# MCU.net
KiCad netlist of a schematic drawn in Altium Designer
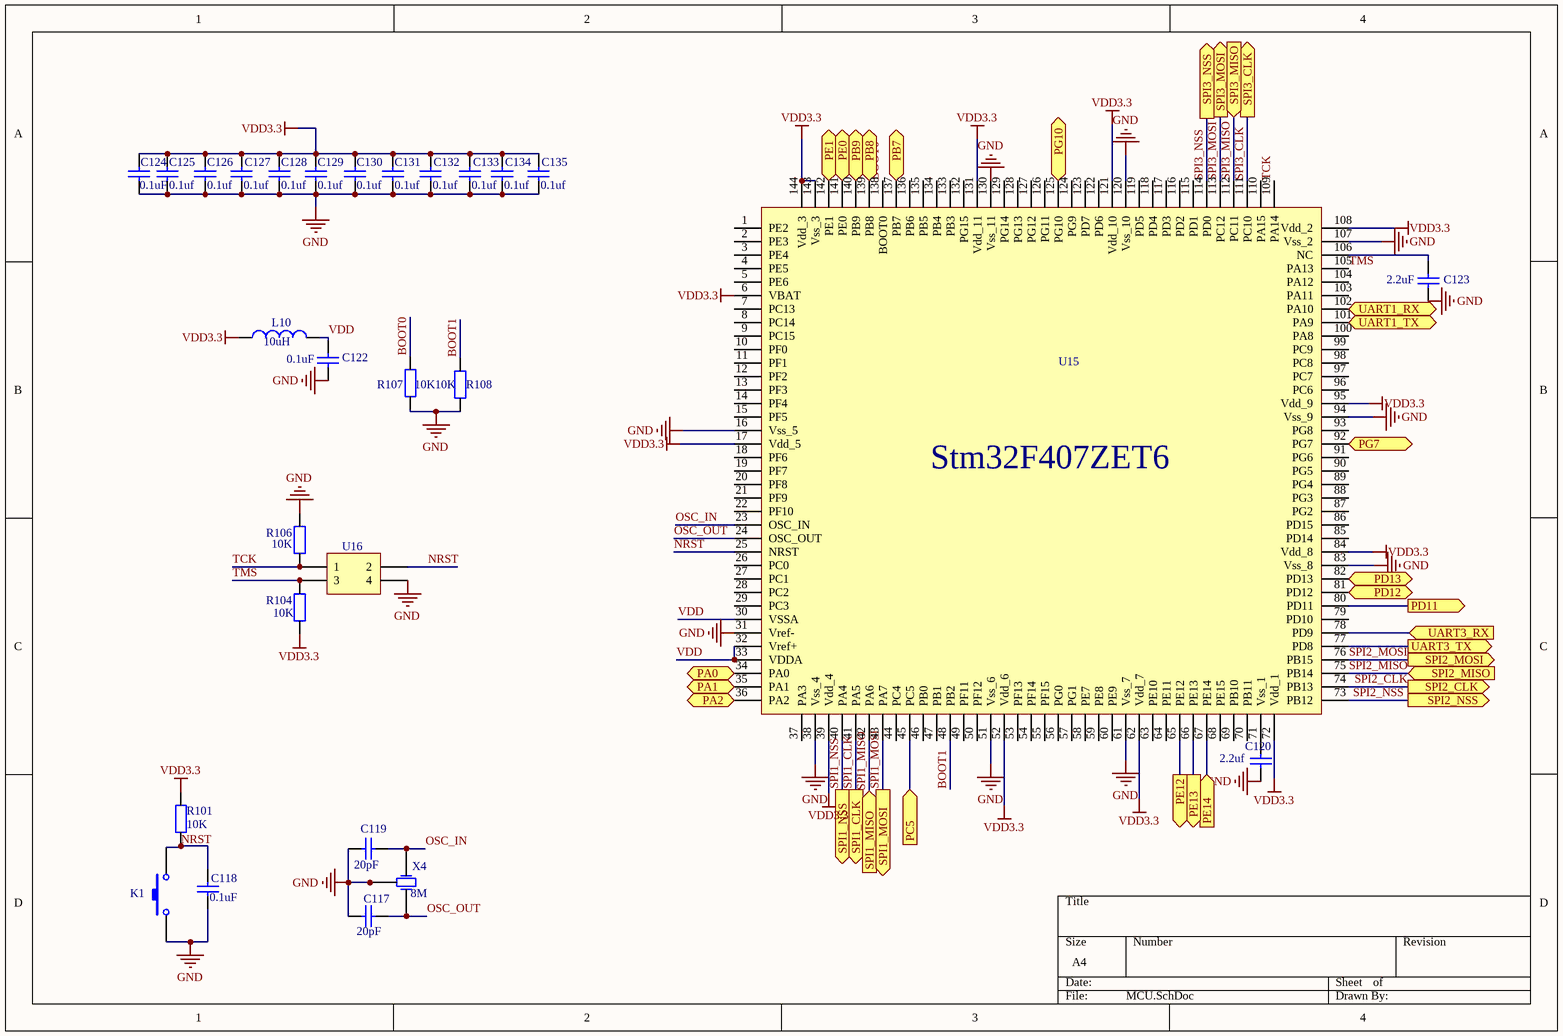
[diagram p0: MCU.SchDoc]

(export (version "E")
  (design (tool "Eeschema 10.0.6"))
  (components
    (comp (ref "C117")
      (value "20pF")
      (footprint "0603")
      (fields (field (name "Comment") "Capacitor-0805"))
      (libsource (lib "原理图库") (part "Capacitor-0805"))
    )
    (comp (ref "C118")
      (value "0.1uF")
      (footprint "0603")
      (fields (field (name "Comment") "Capacitor-0805"))
      (libsource (lib "原理图库") (part "Capacitor-0805"))
    )
    (comp (ref "C119")
      (value "20pF")
      (footprint "0603")
      (fields (field (name "Comment") "Capacitor-0805"))
      (libsource (lib "原理图库") (part "Capacitor-0805"))
    )
    (comp (ref "C120")
      (value "2.2uf")
      (footprint "0603")
      (fields (field (name "Comment") "Capacitor-0603"))
      (libsource (lib "原理图库") (part "Capacitor-0603"))
    )
    (comp (ref "C122")
      (value "0.1uF")
      (footprint "0603")
      (fields (field (name "Comment") "Capacitor-0805"))
      (libsource (lib "集成库—大岐") (part "Capacitor-0805"))
    )
    (comp (ref "C123")
      (value "2.2uF")
      (footprint "0603")
      (fields (field (name "Comment") "Capacitor-0603"))
      (libsource (lib "原理图库") (part "Capacitor-0603"))
    )
    (comp (ref "C124")
      (value "0.1uF")
      (footprint "0603")
      (fields (field (name "Comment") "Capacitor-0805"))
      (libsource (lib "集成库—大岐") (part "Capacitor-0805"))
    )
    (comp (ref "C125")
      (value "0.1uf")
      (footprint "0603")
      (fields (field (name "Comment") "Capacitor-0805"))
      (libsource (lib "集成库—大岐") (part "Capacitor-0805"))
    )
    (comp (ref "C126")
      (value "0.1uf")
      (footprint "0603")
      (fields (field (name "Comment") "Capacitor-0805"))
      (libsource (lib "集成库—大岐") (part "Capacitor-0805"))
    )
    (comp (ref "C127")
      (value "0.1uf")
      (footprint "0603")
      (fields (field (name "Comment") "Capacitor-0805"))
      (libsource (lib "集成库—大岐") (part "Capacitor-0805"))
    )
    (comp (ref "C128")
      (value "0.1uf")
      (footprint "0603")
      (fields (field (name "Comment") "Capacitor-0805"))
      (libsource (lib "集成库—大岐") (part "Capacitor-0805"))
    )
    (comp (ref "C129")
      (value "0.1uf")
      (footprint "0603")
      (fields (field (name "Comment") "Capacitor-0805"))
      (libsource (lib "集成库—大岐") (part "Capacitor-0805"))
    )
    (comp (ref "C130")
      (value "0.1uf")
      (footprint "0603")
      (fields (field (name "Comment") "Capacitor-0805"))
      (libsource (lib "集成库—大岐") (part "Capacitor-0805"))
    )
    (comp (ref "C131")
      (value "0.1uf")
      (footprint "0603")
      (fields (field (name "Comment") "Capacitor-0805"))
      (libsource (lib "集成库—大岐") (part "Capacitor-0805"))
    )
    (comp (ref "C132")
      (value "0.1uf")
      (footprint "0603")
      (fields (field (name "Comment") "Capacitor-0805"))
      (libsource (lib "集成库—大岐") (part "Capacitor-0805"))
    )
    (comp (ref "C133")
      (value "0.1uf")
      (footprint "0603")
      (fields (field (name "Comment") "Capacitor-0805"))
      (libsource (lib "集成库—大岐") (part "Capacitor-0805"))
    )
    (comp (ref "C134")
      (value "0.1uf")
      (footprint "0603")
      (fields (field (name "Comment") "Capacitor-0805"))
      (libsource (lib "集成库—大岐") (part "Capacitor-0805"))
    )
    (comp (ref "C135")
      (value "0.1uf")
      (footprint "0603")
      (fields (field (name "Comment") "Capacitor-0805"))
      (libsource (lib "集成库—大岐") (part "Capacitor-0805"))
    )
    (comp (ref "K1") (value "按键") (footprint "贴片按键") (libsource (lib "原理图库") (part "按键")))
    (comp (ref "L10")
      (value "10uH")
      (footprint "0805")
      (fields (field (name "Comment") "Inductor"))
      (libsource (lib "集成库—大岐") (part "Inductor"))
    )
    (comp (ref "R101")
      (value "10K")
      (footprint "0603")
      (fields (field (name "Comment") "Resistor-0805"))
      (libsource (lib "原理图库") (part "Resistor-0805"))
    )
    (comp (ref "R104")
      (value "10K")
      (footprint "0603")
      (fields (field (name "Comment") "Resistor-0805"))
      (libsource (lib "原理图库") (part "Resistor-0805"))
    )
    (comp (ref "R106")
      (value "10K")
      (footprint "0603")
      (fields (field (name "Comment") "Resistor-0805"))
      (libsource (lib "原理图库") (part "Resistor-0805"))
    )
    (comp (ref "R107")
      (value "10K")
      (footprint "0603")
      (fields (field (name "Comment") "Resistor-0805"))
      (libsource (lib "集成库—大岐") (part "Resistor-0805"))
    )
    (comp (ref "R108")
      (value "10K")
      (footprint "0603")
      (fields (field (name "Comment") "Resistor-0805"))
      (libsource (lib "集成库—大岐") (part "Resistor-0805"))
    )
    (comp (ref "U15")
      (value "STM32F407ZET6")
      (footprint "Stm32f407ZET6 - duplicate")
      (libsource (lib "原理图库") (part "STM32F407ZET6"))
    )
    (comp (ref "U16")
      (value "Header 2X2")
      (footprint "HDR2X2")
      (description "Header, 2-Pin, Dual row")
      (fields (field (name "PUBLISHER") "Altium Limited"))
      (libsource (lib "Miscellaneous Connectors") (part "Header 2X2"))
    )
    (comp (ref "X4")
      (value "8M")
      (footprint "3225无源晶振")
      (fields (field (name "Comment") "3225无源晶振"))
      (libsource (lib "原理图库") (part "3225无源晶振"))
    )
  )
  (nets
    (net (code "1") (name "/BOOT0") (class "Default")
      (node (ref "R107") (pin "2") (pinfunction "2_2") (pintype "passive"))
      (node (ref "U15") (pin "138") (pinfunction "BOOT0_138") (pintype "passive"))
    )
    (net (code "2") (name "/BOOT1") (class "Default")
      (node (ref "R108") (pin "2") (pinfunction "2_2") (pintype "passive"))
      (node (ref "U15") (pin "48") (pinfunction "PB2_48") (pintype "passive"))
    )
    (net (code "3") (name "/NRST") (class "Default")
      (node (ref "C118") (pin "2") (pinfunction "2_2") (pintype "passive"))
      (node (ref "K1") (pin "2") (pinfunction "2_2") (pintype "passive"))
      (node (ref "R101") (pin "1") (pinfunction "1_1") (pintype "passive"))
      (node (ref "U15") (pin "25") (pinfunction "NRST_25") (pintype "passive"))
      (node (ref "U16") (pin "2") (pinfunction "2_2") (pintype "passive"))
    )
    (net (code "4") (name "/OSC_IN") (class "Default")
      (node (ref "C119") (pin "2") (pinfunction "2_2") (pintype "passive"))
      (node (ref "U15") (pin "23") (pinfunction "OSC_IN_23") (pintype "passive"))
      (node (ref "X4") (pin "1") (pinfunction "OSC1_1") (pintype "passive"))
    )
    (net (code "5") (name "/OSC_OUT") (class "Default")
      (node (ref "C117") (pin "2") (pinfunction "2_2") (pintype "passive"))
      (node (ref "U15") (pin "24") (pinfunction "OSC_OUT_24") (pintype "passive"))
      (node (ref "X4") (pin "3") (pinfunction "OSC2_3") (pintype "passive"))
    )
    (net (code "6") (name "/PA0") (class "Default")
      (node (ref "U15") (pin "34") (pinfunction "PA0_34") (pintype "passive"))
    )
    (net (code "7") (name "/PA1") (class "Default")
      (node (ref "U15") (pin "35") (pinfunction "PA1_35") (pintype "passive"))
    )
    (net (code "8") (name "/PA2") (class "Default")
      (node (ref "U15") (pin "36") (pinfunction "PA2_36") (pintype "passive"))
    )
    (net (code "9") (name "/PB7") (class "Default")
      (node (ref "U15") (pin "137") (pinfunction "PB7_137") (pintype "passive"))
    )
    (net (code "10") (name "/PB8") (class "Default")
      (node (ref "U15") (pin "139") (pinfunction "PB8_139") (pintype "passive"))
    )
    (net (code "11") (name "/PB9") (class "Default")
      (node (ref "U15") (pin "140") (pinfunction "PB9_140") (pintype "passive"))
    )
    (net (code "12") (name "/PC5") (class "Default")
      (node (ref "U15") (pin "45") (pinfunction "PC5_45") (pintype "passive"))
    )
    (net (code "13") (name "/PD11") (class "Default")
      (node (ref "U15") (pin "80") (pinfunction "PD11_80") (pintype "passive"))
    )
    (net (code "14") (name "/PD12") (class "Default")
      (node (ref "U15") (pin "81") (pinfunction "PD12_81") (pintype "passive"))
    )
    (net (code "15") (name "/PD13") (class "Default")
      (node (ref "U15") (pin "82") (pinfunction "PD13_82") (pintype "passive"))
    )
    (net (code "16") (name "/PE0") (class "Default")
      (node (ref "U15") (pin "141") (pinfunction "PE0_141") (pintype "passive"))
    )
    (net (code "17") (name "/PE1") (class "Default")
      (node (ref "U15") (pin "142") (pinfunction "PE1_142") (pintype "passive"))
    )
    (net (code "18") (name "/PE12") (class "Default")
      (node (ref "U15") (pin "65") (pinfunction "PE12_65") (pintype "passive"))
    )
    (net (code "19") (name "/PE13") (class "Default")
      (node (ref "U15") (pin "66") (pinfunction "PE13_66") (pintype "passive"))
    )
    (net (code "20") (name "/PE14") (class "Default")
      (node (ref "U15") (pin "67") (pinfunction "PE14_67") (pintype "passive"))
    )
    (net (code "21") (name "/PG7") (class "Default")
      (node (ref "U15") (pin "92") (pinfunction "PG7_92") (pintype "passive"))
    )
    (net (code "22") (name "/PG10") (class "Default")
      (node (ref "U15") (pin "125") (pinfunction "PG10_125") (pintype "passive"))
    )
    (net (code "23") (name "/SPI1_CLK") (class "Default")
      (node (ref "U15") (pin "41") (pinfunction "PA5_41") (pintype "passive"))
    )
    (net (code "24") (name "/SPI1_MISO") (class "Default")
      (node (ref "U15") (pin "42") (pinfunction "PA6_42") (pintype "passive"))
    )
    (net (code "25") (name "/SPI1_MOSI") (class "Default")
      (node (ref "U15") (pin "43") (pinfunction "PA7_43") (pintype "passive"))
    )
    (net (code "26") (name "/SPI1_NSS") (class "Default")
      (node (ref "U15") (pin "40") (pinfunction "PA4_40") (pintype "passive"))
    )
    (net (code "27") (name "/SPI2_CLK") (class "Default")
      (node (ref "U15") (pin "74") (pinfunction "PB13_74") (pintype "passive"))
    )
    (net (code "28") (name "/SPI2_MISO") (class "Default")
      (node (ref "U15") (pin "75") (pinfunction "PB14_75") (pintype "passive"))
    )
    (net (code "29") (name "/SPI2_MOSI") (class "Default")
      (node (ref "U15") (pin "76") (pinfunction "PB15_76") (pintype "passive"))
    )
    (net (code "30") (name "/SPI2_NSS") (class "Default")
      (node (ref "U15") (pin "73") (pinfunction "PB12_73") (pintype "passive"))
    )
    (net (code "31") (name "/SPI3_CLK") (class "Default")
      (node (ref "U15") (pin "111") (pinfunction "PC10_111") (pintype "passive"))
    )
    (net (code "32") (name "/SPI3_MISO") (class "Default")
      (node (ref "U15") (pin "112") (pinfunction "PC11_112") (pintype "passive"))
    )
    (net (code "33") (name "/SPI3_MOSI") (class "Default")
      (node (ref "U15") (pin "113") (pinfunction "PC12_113") (pintype "passive"))
    )
    (net (code "34") (name "/SPI3_NSS") (class "Default")
      (node (ref "U15") (pin "114") (pinfunction "PD0_114") (pintype "passive"))
    )
    (net (code "35") (name "/TCK") (class "Default")
      (node (ref "R106") (pin "1") (pinfunction "1_1") (pintype "passive"))
      (node (ref "U15") (pin "109") (pinfunction "PA14_109") (pintype "passive"))
      (node (ref "U16") (pin "1") (pinfunction "1_1") (pintype "passive"))
    )
    (net (code "36") (name "/TMS") (class "Default")
      (node (ref "R104") (pin "2") (pinfunction "2_2") (pintype "passive"))
      (node (ref "U15") (pin "105") (pinfunction "PA13_105") (pintype "passive"))
      (node (ref "U16") (pin "3") (pinfunction "3_3") (pintype "passive"))
    )
    (net (code "37") (name "/UART1_RX") (class "Default")
      (node (ref "U15") (pin "102") (pinfunction "PA10_102") (pintype "passive"))
    )
    (net (code "38") (name "/UART1_TX") (class "Default")
      (node (ref "U15") (pin "101") (pinfunction "PA9_101") (pintype "passive"))
    )
    (net (code "39") (name "/UART3_RX") (class "Default")
      (node (ref "U15") (pin "78") (pinfunction "PD9_78") (pintype "passive"))
    )
    (net (code "40") (name "/UART3_TX") (class "Default")
      (node (ref "U15") (pin "77") (pinfunction "PD8_77") (pintype "passive"))
    )
    (net (code "41") (name "/VDD") (class "Default")
      (node (ref "C122") (pin "2") (pinfunction "2_2") (pintype "passive"))
      (node (ref "L10") (pin "2") (pinfunction "2_2") (pintype "passive"))
      (node (ref "U15") (pin "30") (pinfunction "VSSA_30") (pintype "passive"))
      (node (ref "U15") (pin "32") (pinfunction "Vref+_32") (pintype "passive"))
      (node (ref "U15") (pin "33") (pinfunction "VDDA_33") (pintype "passive"))
    )
    (net (code "42") (name "GND") (class "Default")
      (node (ref "C117") (pin "1") (pinfunction "1_1") (pintype "passive"))
      (node (ref "C118") (pin "1") (pinfunction "1_1") (pintype "passive"))
      (node (ref "C119") (pin "1") (pinfunction "1_1") (pintype "passive"))
      (node (ref "C120") (pin "1") (pinfunction "1_1") (pintype "passive"))
      (node (ref "C122") (pin "1") (pinfunction "1_1") (pintype "passive"))
      (node (ref "C123") (pin "1") (pinfunction "1_1") (pintype "passive"))
      (node (ref "C124") (pin "1") (pinfunction "1_1") (pintype "passive"))
      (node (ref "C125") (pin "1") (pinfunction "1_1") (pintype "passive"))
      (node (ref "C126") (pin "1") (pinfunction "1_1") (pintype "passive"))
      (node (ref "C127") (pin "1") (pinfunction "1_1") (pintype "passive"))
      (node (ref "C128") (pin "1") (pinfunction "1_1") (pintype "passive"))
      (node (ref "C129") (pin "1") (pinfunction "1_1") (pintype "passive"))
      (node (ref "C130") (pin "1") (pinfunction "1_1") (pintype "passive"))
      (node (ref "C131") (pin "1") (pinfunction "1_1") (pintype "passive"))
      (node (ref "C132") (pin "1") (pinfunction "1_1") (pintype "passive"))
      (node (ref "C133") (pin "1") (pinfunction "1_1") (pintype "passive"))
      (node (ref "C134") (pin "1") (pinfunction "1_1") (pintype "passive"))
      (node (ref "C135") (pin "1") (pinfunction "1_1") (pintype "passive"))
      (node (ref "K1") (pin "1") (pinfunction "1_1") (pintype "passive"))
      (node (ref "R106") (pin "2") (pinfunction "2_2") (pintype "passive"))
      (node (ref "R107") (pin "1") (pinfunction "1_1") (pintype "passive"))
      (node (ref "R108") (pin "1") (pinfunction "1_1") (pintype "passive"))
      (node (ref "U15") (pin "107") (pinfunction "Vss_2_107") (pintype "passive"))
      (node (ref "U15") (pin "120") (pinfunction "Vss_10_120") (pintype "passive"))
      (node (ref "U15") (pin "130") (pinfunction "Vss_11_130") (pintype "passive"))
      (node (ref "U15") (pin "16") (pinfunction "Vss_5_16") (pintype "passive"))
      (node (ref "U15") (pin "31") (pinfunction "Vref-_31") (pintype "passive"))
      (node (ref "U15") (pin "38") (pinfunction "Vss_4_38") (pintype "passive"))
      (node (ref "U15") (pin "51") (pinfunction "Vss_6_51") (pintype "passive"))
      (node (ref "U15") (pin "61") (pinfunction "Vss_7_61") (pintype "passive"))
      (node (ref "U15") (pin "83") (pinfunction "Vss_8_83") (pintype "passive"))
      (node (ref "U15") (pin "94") (pinfunction "Vss_9_94") (pintype "passive"))
      (node (ref "U16") (pin "4") (pinfunction "4_4") (pintype "passive"))
      (node (ref "X4") (pin "2") (pinfunction "GND_2") (pintype "passive"))
      (node (ref "X4") (pin "4") (pinfunction "GND_4") (pintype "passive"))
    )
    (net (code "43") (name "Net-(U15-NC)") (class "Default")
      (node (ref "C123") (pin "2") (pinfunction "2_2") (pintype "passive"))
      (node (ref "U15") (pin "106") (pinfunction "NC_106") (pintype "passive"))
    )
    (net (code "44") (name "Net-(U15-Vss_1)") (class "Default")
      (node (ref "C120") (pin "2") (pinfunction "2_2") (pintype "passive"))
      (node (ref "U15") (pin "71") (pinfunction "Vss_1_71") (pintype "passive"))
    )
    (net (code "45") (name "VDD3.3") (class "Default")
      (node (ref "C124") (pin "2") (pinfunction "2_2") (pintype "passive"))
      (node (ref "C125") (pin "2") (pinfunction "2_2") (pintype "passive"))
      (node (ref "C126") (pin "2") (pinfunction "2_2") (pintype "passive"))
      (node (ref "C127") (pin "2") (pinfunction "2_2") (pintype "passive"))
      (node (ref "C128") (pin "2") (pinfunction "2_2") (pintype "passive"))
      (node (ref "C129") (pin "2") (pinfunction "2_2") (pintype "passive"))
      (node (ref "C130") (pin "2") (pinfunction "2_2") (pintype "passive"))
      (node (ref "C131") (pin "2") (pinfunction "2_2") (pintype "passive"))
      (node (ref "C132") (pin "2") (pinfunction "2_2") (pintype "passive"))
      (node (ref "C133") (pin "2") (pinfunction "2_2") (pintype "passive"))
      (node (ref "C134") (pin "2") (pinfunction "2_2") (pintype "passive"))
      (node (ref "C135") (pin "2") (pinfunction "2_2") (pintype "passive"))
      (node (ref "L10") (pin "1") (pinfunction "1_1") (pintype "passive"))
      (node (ref "R101") (pin "2") (pinfunction "2_2") (pintype "passive"))
      (node (ref "R104") (pin "1") (pinfunction "1_1") (pintype "passive"))
      (node (ref "U15") (pin "108") (pinfunction "Vdd_2_108") (pintype "passive"))
      (node (ref "U15") (pin "121") (pinfunction "Vdd_10_121") (pintype "passive"))
      (node (ref "U15") (pin "131") (pinfunction "Vdd_11_131") (pintype "passive"))
      (node (ref "U15") (pin "143") (pinfunction "Vss_3_143") (pintype "passive"))
      (node (ref "U15") (pin "144") (pinfunction "Vdd_3_144") (pintype "passive"))
      (node (ref "U15") (pin "17") (pinfunction "Vdd_5_17") (pintype "passive"))
      (node (ref "U15") (pin "39") (pinfunction "Vdd_4_39") (pintype "passive"))
      (node (ref "U15") (pin "52") (pinfunction "Vdd_6_52") (pintype "passive"))
      (node (ref "U15") (pin "6") (pinfunction "VBAT_6") (pintype "passive"))
      (node (ref "U15") (pin "62") (pinfunction "Vdd_7_62") (pintype "passive"))
      (node (ref "U15") (pin "72") (pinfunction "Vdd_1_72") (pintype "passive"))
      (node (ref "U15") (pin "84") (pinfunction "Vdd_8_84") (pintype "passive"))
      (node (ref "U15") (pin "95") (pinfunction "Vdd_9_95") (pintype "passive"))
    )
    (net (code "46") (name "unconnected-(U15-PA3-Pad37)") (class "Default")
      (node (ref "U15") (pin "37") (pinfunction "PA3_37") (pintype "passive"))
    )
    (net (code "47") (name "unconnected-(U15-PA8-Pad100)") (class "Default")
      (node (ref "U15") (pin "100") (pinfunction "PA8_100") (pintype "passive"))
    )
    (net (code "48") (name "unconnected-(U15-PA11-Pad103)") (class "Default")
      (node (ref "U15") (pin "103") (pinfunction "PA11_103") (pintype "passive"))
    )
    (net (code "49") (name "unconnected-(U15-PA12-Pad104)") (class "Default")
      (node (ref "U15") (pin "104") (pinfunction "PA12_104") (pintype "passive"))
    )
    (net (code "50") (name "unconnected-(U15-PA15-Pad110)") (class "Default")
      (node (ref "U15") (pin "110") (pinfunction "PA15_110") (pintype "passive"))
    )
    (net (code "51") (name "unconnected-(U15-PB0-Pad46)") (class "Default")
      (node (ref "U15") (pin "46") (pinfunction "PB0_46") (pintype "passive"))
    )
    (net (code "52") (name "unconnected-(U15-PB1-Pad47)") (class "Default")
      (node (ref "U15") (pin "47") (pinfunction "PB1_47") (pintype "passive"))
    )
    (net (code "53") (name "unconnected-(U15-PB3-Pad133)") (class "Default")
      (node (ref "U15") (pin "133") (pinfunction "PB3_133") (pintype "passive"))
    )
    (net (code "54") (name "unconnected-(U15-PB4-Pad134)") (class "Default")
      (node (ref "U15") (pin "134") (pinfunction "PB4_134") (pintype "passive"))
    )
    (net (code "55") (name "unconnected-(U15-PB5-Pad135)") (class "Default")
      (node (ref "U15") (pin "135") (pinfunction "PB5_135") (pintype "passive"))
    )
    (net (code "56") (name "unconnected-(U15-PB6-Pad136)") (class "Default")
      (node (ref "U15") (pin "136") (pinfunction "PB6_136") (pintype "passive"))
    )
    (net (code "57") (name "unconnected-(U15-PB10-Pad69)") (class "Default")
      (node (ref "U15") (pin "69") (pinfunction "PB10_69") (pintype "passive"))
    )
    (net (code "58") (name "unconnected-(U15-PB11-Pad70)") (class "Default")
      (node (ref "U15") (pin "70") (pinfunction "PB11_70") (pintype "passive"))
    )
    (net (code "59") (name "unconnected-(U15-PC0-Pad26)") (class "Default")
      (node (ref "U15") (pin "26") (pinfunction "PC0_26") (pintype "passive"))
    )
    (net (code "60") (name "unconnected-(U15-PC1-Pad27)") (class "Default")
      (node (ref "U15") (pin "27") (pinfunction "PC1_27") (pintype "passive"))
    )
    (net (code "61") (name "unconnected-(U15-PC2-Pad28)") (class "Default")
      (node (ref "U15") (pin "28") (pinfunction "PC2_28") (pintype "passive"))
    )
    (net (code "62") (name "unconnected-(U15-PC3-Pad29)") (class "Default")
      (node (ref "U15") (pin "29") (pinfunction "PC3_29") (pintype "passive"))
    )
    (net (code "63") (name "unconnected-(U15-PC4-Pad44)") (class "Default")
      (node (ref "U15") (pin "44") (pinfunction "PC4_44") (pintype "passive"))
    )
    (net (code "64") (name "unconnected-(U15-PC6-Pad96)") (class "Default")
      (node (ref "U15") (pin "96") (pinfunction "PC6_96") (pintype "passive"))
    )
    (net (code "65") (name "unconnected-(U15-PC7-Pad97)") (class "Default")
      (node (ref "U15") (pin "97") (pinfunction "PC7_97") (pintype "passive"))
    )
    (net (code "66") (name "unconnected-(U15-PC8-Pad98)") (class "Default")
      (node (ref "U15") (pin "98") (pinfunction "PC8_98") (pintype "passive"))
    )
    (net (code "67") (name "unconnected-(U15-PC9-Pad99)") (class "Default")
      (node (ref "U15") (pin "99") (pinfunction "PC9_99") (pintype "passive"))
    )
    (net (code "68") (name "unconnected-(U15-PC13-Pad7)") (class "Default")
      (node (ref "U15") (pin "7") (pinfunction "PC13_7") (pintype "passive"))
    )
    (net (code "69") (name "unconnected-(U15-PC14-Pad8)") (class "Default")
      (node (ref "U15") (pin "8") (pinfunction "PC14_8") (pintype "passive"))
    )
    (net (code "70") (name "unconnected-(U15-PC15-Pad9)") (class "Default")
      (node (ref "U15") (pin "9") (pinfunction "PC15_9") (pintype "passive"))
    )
    (net (code "71") (name "unconnected-(U15-PD1-Pad115)") (class "Default")
      (node (ref "U15") (pin "115") (pinfunction "PD1_115") (pintype "passive"))
    )
    (net (code "72") (name "unconnected-(U15-PD2-Pad116)") (class "Default")
      (node (ref "U15") (pin "116") (pinfunction "PD2_116") (pintype "passive"))
    )
    (net (code "73") (name "unconnected-(U15-PD3-Pad117)") (class "Default")
      (node (ref "U15") (pin "117") (pinfunction "PD3_117") (pintype "passive"))
    )
    (net (code "74") (name "unconnected-(U15-PD4-Pad118)") (class "Default")
      (node (ref "U15") (pin "118") (pinfunction "PD4_118") (pintype "passive"))
    )
    (net (code "75") (name "unconnected-(U15-PD5-Pad119)") (class "Default")
      (node (ref "U15") (pin "119") (pinfunction "PD5_119") (pintype "passive"))
    )
    (net (code "76") (name "unconnected-(U15-PD6-Pad122)") (class "Default")
      (node (ref "U15") (pin "122") (pinfunction "PD6_122") (pintype "passive"))
    )
    (net (code "77") (name "unconnected-(U15-PD7-Pad123)") (class "Default")
      (node (ref "U15") (pin "123") (pinfunction "PD7_123") (pintype "passive"))
    )
    (net (code "78") (name "unconnected-(U15-PD10-Pad79)") (class "Default")
      (node (ref "U15") (pin "79") (pinfunction "PD10_79") (pintype "passive"))
    )
    (net (code "79") (name "unconnected-(U15-PD14-Pad85)") (class "Default")
      (node (ref "U15") (pin "85") (pinfunction "PD14_85") (pintype "passive"))
    )
    (net (code "80") (name "unconnected-(U15-PD15-Pad86)") (class "Default")
      (node (ref "U15") (pin "86") (pinfunction "PD15_86") (pintype "passive"))
    )
    (net (code "81") (name "unconnected-(U15-PE2-Pad1)") (class "Default")
      (node (ref "U15") (pin "1") (pinfunction "PE2_1") (pintype "passive"))
    )
    (net (code "82") (name "unconnected-(U15-PE3-Pad2)") (class "Default")
      (node (ref "U15") (pin "2") (pinfunction "PE3_2") (pintype "passive"))
    )
    (net (code "83") (name "unconnected-(U15-PE4-Pad3)") (class "Default")
      (node (ref "U15") (pin "3") (pinfunction "PE4_3") (pintype "passive"))
    )
    (net (code "84") (name "unconnected-(U15-PE5-Pad4)") (class "Default")
      (node (ref "U15") (pin "4") (pinfunction "PE5_4") (pintype "passive"))
    )
    (net (code "85") (name "unconnected-(U15-PE6-Pad5)") (class "Default")
      (node (ref "U15") (pin "5") (pinfunction "PE6_5") (pintype "passive"))
    )
    (net (code "86") (name "unconnected-(U15-PE7-Pad58)") (class "Default")
      (node (ref "U15") (pin "58") (pinfunction "PE7_58") (pintype "passive"))
    )
    (net (code "87") (name "unconnected-(U15-PE8-Pad59)") (class "Default")
      (node (ref "U15") (pin "59") (pinfunction "PE8_59") (pintype "passive"))
    )
    (net (code "88") (name "unconnected-(U15-PE9-Pad60)") (class "Default")
      (node (ref "U15") (pin "60") (pinfunction "PE9_60") (pintype "passive"))
    )
    (net (code "89") (name "unconnected-(U15-PE10-Pad63)") (class "Default")
      (node (ref "U15") (pin "63") (pinfunction "PE10_63") (pintype "passive"))
    )
    (net (code "90") (name "unconnected-(U15-PE11-Pad64)") (class "Default")
      (node (ref "U15") (pin "64") (pinfunction "PE11_64") (pintype "passive"))
    )
    (net (code "91") (name "unconnected-(U15-PE15-Pad68)") (class "Default")
      (node (ref "U15") (pin "68") (pinfunction "PE15_68") (pintype "passive"))
    )
    (net (code "92") (name "unconnected-(U15-PF0-Pad10)") (class "Default")
      (node (ref "U15") (pin "10") (pinfunction "PF0_10") (pintype "passive"))
    )
    (net (code "93") (name "unconnected-(U15-PF1-Pad11)") (class "Default")
      (node (ref "U15") (pin "11") (pinfunction "PF1_11") (pintype "passive"))
    )
    (net (code "94") (name "unconnected-(U15-PF2-Pad12)") (class "Default")
      (node (ref "U15") (pin "12") (pinfunction "PF2_12") (pintype "passive"))
    )
    (net (code "95") (name "unconnected-(U15-PF3-Pad13)") (class "Default")
      (node (ref "U15") (pin "13") (pinfunction "PF3_13") (pintype "passive"))
    )
    (net (code "96") (name "unconnected-(U15-PF4-Pad14)") (class "Default")
      (node (ref "U15") (pin "14") (pinfunction "PF4_14") (pintype "passive"))
    )
    (net (code "97") (name "unconnected-(U15-PF5-Pad15)") (class "Default")
      (node (ref "U15") (pin "15") (pinfunction "PF5_15") (pintype "passive"))
    )
    (net (code "98") (name "unconnected-(U15-PF6-Pad18)") (class "Default")
      (node (ref "U15") (pin "18") (pinfunction "PF6_18") (pintype "passive"))
    )
    (net (code "99") (name "unconnected-(U15-PF7-Pad19)") (class "Default")
      (node (ref "U15") (pin "19") (pinfunction "PF7_19") (pintype "passive"))
    )
    (net (code "100") (name "unconnected-(U15-PF8-Pad20)") (class "Default")
      (node (ref "U15") (pin "20") (pinfunction "PF8_20") (pintype "passive"))
    )
    (net (code "101") (name "unconnected-(U15-PF9-Pad21)") (class "Default")
      (node (ref "U15") (pin "21") (pinfunction "PF9_21") (pintype "passive"))
    )
    (net (code "102") (name "unconnected-(U15-PF10-Pad22)") (class "Default")
      (node (ref "U15") (pin "22") (pinfunction "PF10_22") (pintype "passive"))
    )
    (net (code "103") (name "unconnected-(U15-PF11-Pad49)") (class "Default")
      (node (ref "U15") (pin "49") (pinfunction "PF11_49") (pintype "passive"))
    )
    (net (code "104") (name "unconnected-(U15-PF12-Pad50)") (class "Default")
      (node (ref "U15") (pin "50") (pinfunction "PF12_50") (pintype "passive"))
    )
    (net (code "105") (name "unconnected-(U15-PF13-Pad53)") (class "Default")
      (node (ref "U15") (pin "53") (pinfunction "PF13_53") (pintype "passive"))
    )
    (net (code "106") (name "unconnected-(U15-PF14-Pad54)") (class "Default")
      (node (ref "U15") (pin "54") (pinfunction "PF14_54") (pintype "passive"))
    )
    (net (code "107") (name "unconnected-(U15-PF15-Pad55)") (class "Default")
      (node (ref "U15") (pin "55") (pinfunction "PF15_55") (pintype "passive"))
    )
    (net (code "108") (name "unconnected-(U15-PG0-Pad56)") (class "Default")
      (node (ref "U15") (pin "56") (pinfunction "PG0_56") (pintype "passive"))
    )
    (net (code "109") (name "unconnected-(U15-PG1-Pad57)") (class "Default")
      (node (ref "U15") (pin "57") (pinfunction "PG1_57") (pintype "passive"))
    )
    (net (code "110") (name "unconnected-(U15-PG2-Pad87)") (class "Default")
      (node (ref "U15") (pin "87") (pinfunction "PG2_87") (pintype "passive"))
    )
    (net (code "111") (name "unconnected-(U15-PG3-Pad88)") (class "Default")
      (node (ref "U15") (pin "88") (pinfunction "PG3_88") (pintype "passive"))
    )
    (net (code "112") (name "unconnected-(U15-PG4-Pad89)") (class "Default")
      (node (ref "U15") (pin "89") (pinfunction "PG4_89") (pintype "passive"))
    )
    (net (code "113") (name "unconnected-(U15-PG5-Pad90)") (class "Default")
      (node (ref "U15") (pin "90") (pinfunction "PG5_90") (pintype "passive"))
    )
    (net (code "114") (name "unconnected-(U15-PG6-Pad91)") (class "Default")
      (node (ref "U15") (pin "91") (pinfunction "PG6_91") (pintype "passive"))
    )
    (net (code "115") (name "unconnected-(U15-PG8-Pad93)") (class "Default")
      (node (ref "U15") (pin "93") (pinfunction "PG8_93") (pintype "passive"))
    )
    (net (code "116") (name "unconnected-(U15-PG9-Pad124)") (class "Default")
      (node (ref "U15") (pin "124") (pinfunction "PG9_124") (pintype "passive"))
    )
    (net (code "117") (name "unconnected-(U15-PG11-Pad126)") (class "Default")
      (node (ref "U15") (pin "126") (pinfunction "PG11_126") (pintype "passive"))
    )
    (net (code "118") (name "unconnected-(U15-PG12-Pad127)") (class "Default")
      (node (ref "U15") (pin "127") (pinfunction "PG12_127") (pintype "passive"))
    )
    (net (code "119") (name "unconnected-(U15-PG13-Pad128)") (class "Default")
      (node (ref "U15") (pin "128") (pinfunction "PG13_128") (pintype "passive"))
    )
    (net (code "120") (name "unconnected-(U15-PG14-Pad129)") (class "Default")
      (node (ref "U15") (pin "129") (pinfunction "PG14_129") (pintype "passive"))
    )
    (net (code "121") (name "unconnected-(U15-PG15-Pad132)") (class "Default")
      (node (ref "U15") (pin "132") (pinfunction "PG15_132") (pintype "passive"))
    )
  )
)
